# JR_expansion.net
KiCad netlist of a schematic drawn in Altium Designer
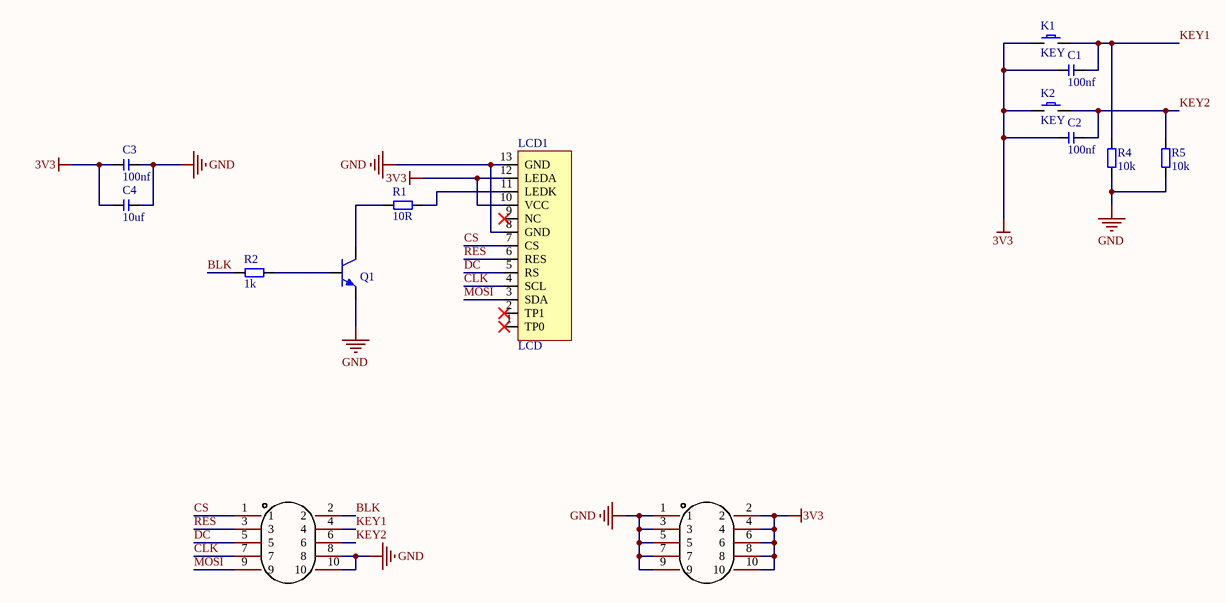
[diagram p0: JR_expansion.SchDoc]

(export (version "E")
  (design (tool "Eeschema 10.0.6"))
  (components
    (comp (ref "C1")
      (value "100nf")
      (footprint "C0603")
      (description "无极电容")
      (libsource (lib "Robocon_V3.0") (part "CAP"))
    )
    (comp (ref "C2")
      (value "100nf")
      (footprint "C0603")
      (description "无极电容")
      (libsource (lib "Robocon_V3.0") (part "CAP"))
    )
    (comp (ref "C3")
      (value "100nf")
      (footprint "C0603")
      (description "无极电容")
      (libsource (lib "Robocon_V3.0") (part "CAP"))
    )
    (comp (ref "C4")
      (value "10uf")
      (footprint "C0603")
      (description "无极电容")
      (libsource (lib "Robocon_V3.0") (part "CAP"))
    )
    (comp (ref "K1") (value "KEY") (footprint "Key") (libsource (lib "altium-import") (part "root_0_KEY_")))
    (comp (ref "K2") (value "KEY") (footprint "Key") (libsource (lib "altium-import") (part "root_0_KEY_")))
    (comp (ref "LCD1")
      (value "LCD")
      (footprint "lcd 0.96‘")
      (libsource (lib "altium-import") (part "root_0_LCD_"))
    )
    (comp (ref "Q1")
      (value "BJT_NPN")
      (footprint "SOT23")
      (description "Transistor")
      (libsource (lib "Robocon_V3.0") (part "BJT_NPN"))
    )
    (comp (ref "R1")
      (value "10R")
      (footprint "R0603")
      (description "电阻")
      (libsource (lib "Robocon_V3.0") (part "RES"))
    )
    (comp (ref "R2")
      (value "1k")
      (footprint "R0603")
      (description "电阻")
      (libsource (lib "Robocon_V3.0") (part "RES"))
    )
    (comp (ref "R4")
      (value "10k")
      (footprint "R0603")
      (description "电阻")
      (libsource (lib "Robocon_V3.0") (part "RES"))
    )
    (comp (ref "R5")
      (value "10k")
      (footprint "R0603")
      (description "电阻")
      (libsource (lib "Robocon_V3.0") (part "RES"))
    )
    (comp (ref "U1")
      (value "2343U-205CNG1SNT01")
      (footprint "CONN-SMD_10P-P1.27_XFCN_PZ127VS-12-10-H10-A38")
      (fields (field (name "MANUFACTURER") "华宇创"))
      (libsource (lib "altium-import") (part "root_0_1.27排针 2*5P_"))
    )
    (comp (ref "U2")
      (value "2343U-205CNG1SNT01")
      (footprint "CONN-SMD_10P-P1.27_XFCN_PZ127VS-12-10-H10-A38")
      (fields (field (name "MANUFACTURER") "华宇创"))
      (libsource (lib "altium-import") (part "root_0_1.27排针 2*5P_"))
    )
  )
  (nets
    (net (code "1") (name "/BLK") (class "Default")
      (node (ref "R2") (pin "1") (pinfunction "1_1") (pintype "passive"))
      (node (ref "U1") (pin "2") (pinfunction "2_2") (pintype "passive"))
    )
    (net (code "2") (name "/CLK") (class "Default")
      (node (ref "LCD1") (pin "4") (pinfunction "SCL_4") (pintype "passive"))
      (node (ref "U1") (pin "7") (pinfunction "7_7") (pintype "passive"))
    )
    (net (code "3") (name "/CS") (class "Default")
      (node (ref "LCD1") (pin "7") (pinfunction "CS_7") (pintype "passive"))
      (node (ref "U1") (pin "1") (pinfunction "1_1") (pintype "passive"))
    )
    (net (code "4") (name "/DC") (class "Default")
      (node (ref "LCD1") (pin "5") (pinfunction "RS_5") (pintype "passive"))
      (node (ref "U1") (pin "5") (pinfunction "5_5") (pintype "passive"))
    )
    (net (code "5") (name "/KEY1") (class "Default")
      (node (ref "C1") (pin "2") (pinfunction "2_2") (pintype "passive"))
      (node (ref "K1") (pin "2") (pinfunction "2_2") (pintype "passive"))
      (node (ref "R4") (pin "2") (pinfunction "2_2") (pintype "passive"))
      (node (ref "U1") (pin "4") (pinfunction "4_4") (pintype "passive"))
    )
    (net (code "6") (name "/KEY2") (class "Default")
      (node (ref "C2") (pin "2") (pinfunction "2_2") (pintype "passive"))
      (node (ref "K2") (pin "2") (pinfunction "2_2") (pintype "passive"))
      (node (ref "R5") (pin "2") (pinfunction "2_2") (pintype "passive"))
      (node (ref "U1") (pin "6") (pinfunction "6_6") (pintype "passive"))
    )
    (net (code "7") (name "/MOSI") (class "Default")
      (node (ref "LCD1") (pin "3") (pinfunction "SDA_3") (pintype "passive"))
      (node (ref "U1") (pin "9") (pinfunction "9_9") (pintype "passive"))
    )
    (net (code "8") (name "/RES") (class "Default")
      (node (ref "LCD1") (pin "6") (pinfunction "RES_6") (pintype "passive"))
      (node (ref "U1") (pin "3") (pinfunction "3_3") (pintype "passive"))
    )
    (net (code "9") (name "3V3") (class "Default")
      (node (ref "C1") (pin "1") (pinfunction "1_1") (pintype "passive"))
      (node (ref "C2") (pin "1") (pinfunction "1_1") (pintype "passive"))
      (node (ref "C3") (pin "1") (pinfunction "1_1") (pintype "passive"))
      (node (ref "C4") (pin "1") (pinfunction "1_1") (pintype "passive"))
      (node (ref "K1") (pin "1") (pinfunction "1_1") (pintype "passive"))
      (node (ref "K2") (pin "1") (pinfunction "1_1") (pintype "passive"))
      (node (ref "LCD1") (pin "10") (pinfunction "VCC_10") (pintype "passive"))
      (node (ref "LCD1") (pin "12") (pinfunction "LEDA_12") (pintype "passive"))
      (node (ref "U2") (pin "10") (pinfunction "10_10") (pintype "passive"))
      (node (ref "U2") (pin "2") (pinfunction "2_2") (pintype "passive"))
      (node (ref "U2") (pin "4") (pinfunction "4_4") (pintype "passive"))
      (node (ref "U2") (pin "6") (pinfunction "6_6") (pintype "passive"))
      (node (ref "U2") (pin "8") (pinfunction "8_8") (pintype "passive"))
    )
    (net (code "10") (name "GND") (class "Default")
      (node (ref "C3") (pin "2") (pinfunction "2_2") (pintype "passive"))
      (node (ref "C4") (pin "2") (pinfunction "2_2") (pintype "passive"))
      (node (ref "LCD1") (pin "13") (pinfunction "GND_13") (pintype "passive"))
      (node (ref "LCD1") (pin "8") (pinfunction "GND_8") (pintype "passive"))
      (node (ref "Q1") (pin "2") (pinfunction "E_2") (pintype "passive"))
      (node (ref "R4") (pin "1") (pinfunction "1_1") (pintype "passive"))
      (node (ref "R5") (pin "1") (pinfunction "1_1") (pintype "passive"))
      (node (ref "U1") (pin "10") (pinfunction "10_10") (pintype "passive"))
      (node (ref "U1") (pin "8") (pinfunction "8_8") (pintype "passive"))
      (node (ref "U2") (pin "1") (pinfunction "1_1") (pintype "passive"))
      (node (ref "U2") (pin "3") (pinfunction "3_3") (pintype "passive"))
      (node (ref "U2") (pin "5") (pinfunction "5_5") (pintype "passive"))
      (node (ref "U2") (pin "7") (pinfunction "7_7") (pintype "passive"))
      (node (ref "U2") (pin "9") (pinfunction "9_9") (pintype "passive"))
    )
    (net (code "11") (name "Net-(LCD1-LEDK)") (class "Default")
      (node (ref "LCD1") (pin "11") (pinfunction "LEDK_11") (pintype "passive"))
      (node (ref "R1") (pin "2") (pinfunction "2_2") (pintype "passive"))
    )
    (net (code "12") (name "Net-(Q1-B)") (class "Default")
      (node (ref "Q1") (pin "1") (pinfunction "B_1") (pintype "passive"))
      (node (ref "R2") (pin "2") (pinfunction "2_2") (pintype "passive"))
    )
    (net (code "13") (name "Net-(Q1-C)") (class "Default")
      (node (ref "Q1") (pin "3") (pinfunction "C_3") (pintype "passive"))
      (node (ref "R1") (pin "1") (pinfunction "1_1") (pintype "passive"))
    )
    (net (code "14") (name "unconnected-(LCD1-NC-Pad9)") (class "Default")
      (node (ref "LCD1") (pin "9") (pinfunction "NC_9") (pintype "passive+no_connect"))
    )
    (net (code "15") (name "unconnected-(LCD1-TP0-Pad1)") (class "Default")
      (node (ref "LCD1") (pin "1") (pinfunction "TP0_1") (pintype "passive+no_connect"))
    )
    (net (code "16") (name "unconnected-(LCD1-TP1-Pad2)") (class "Default")
      (node (ref "LCD1") (pin "2") (pinfunction "TP1_2") (pintype "passive+no_connect"))
    )
  )
)
